# stm32-lqfp64-enc28j60.net
KiCad netlist of a schematic drawn in EAGLE
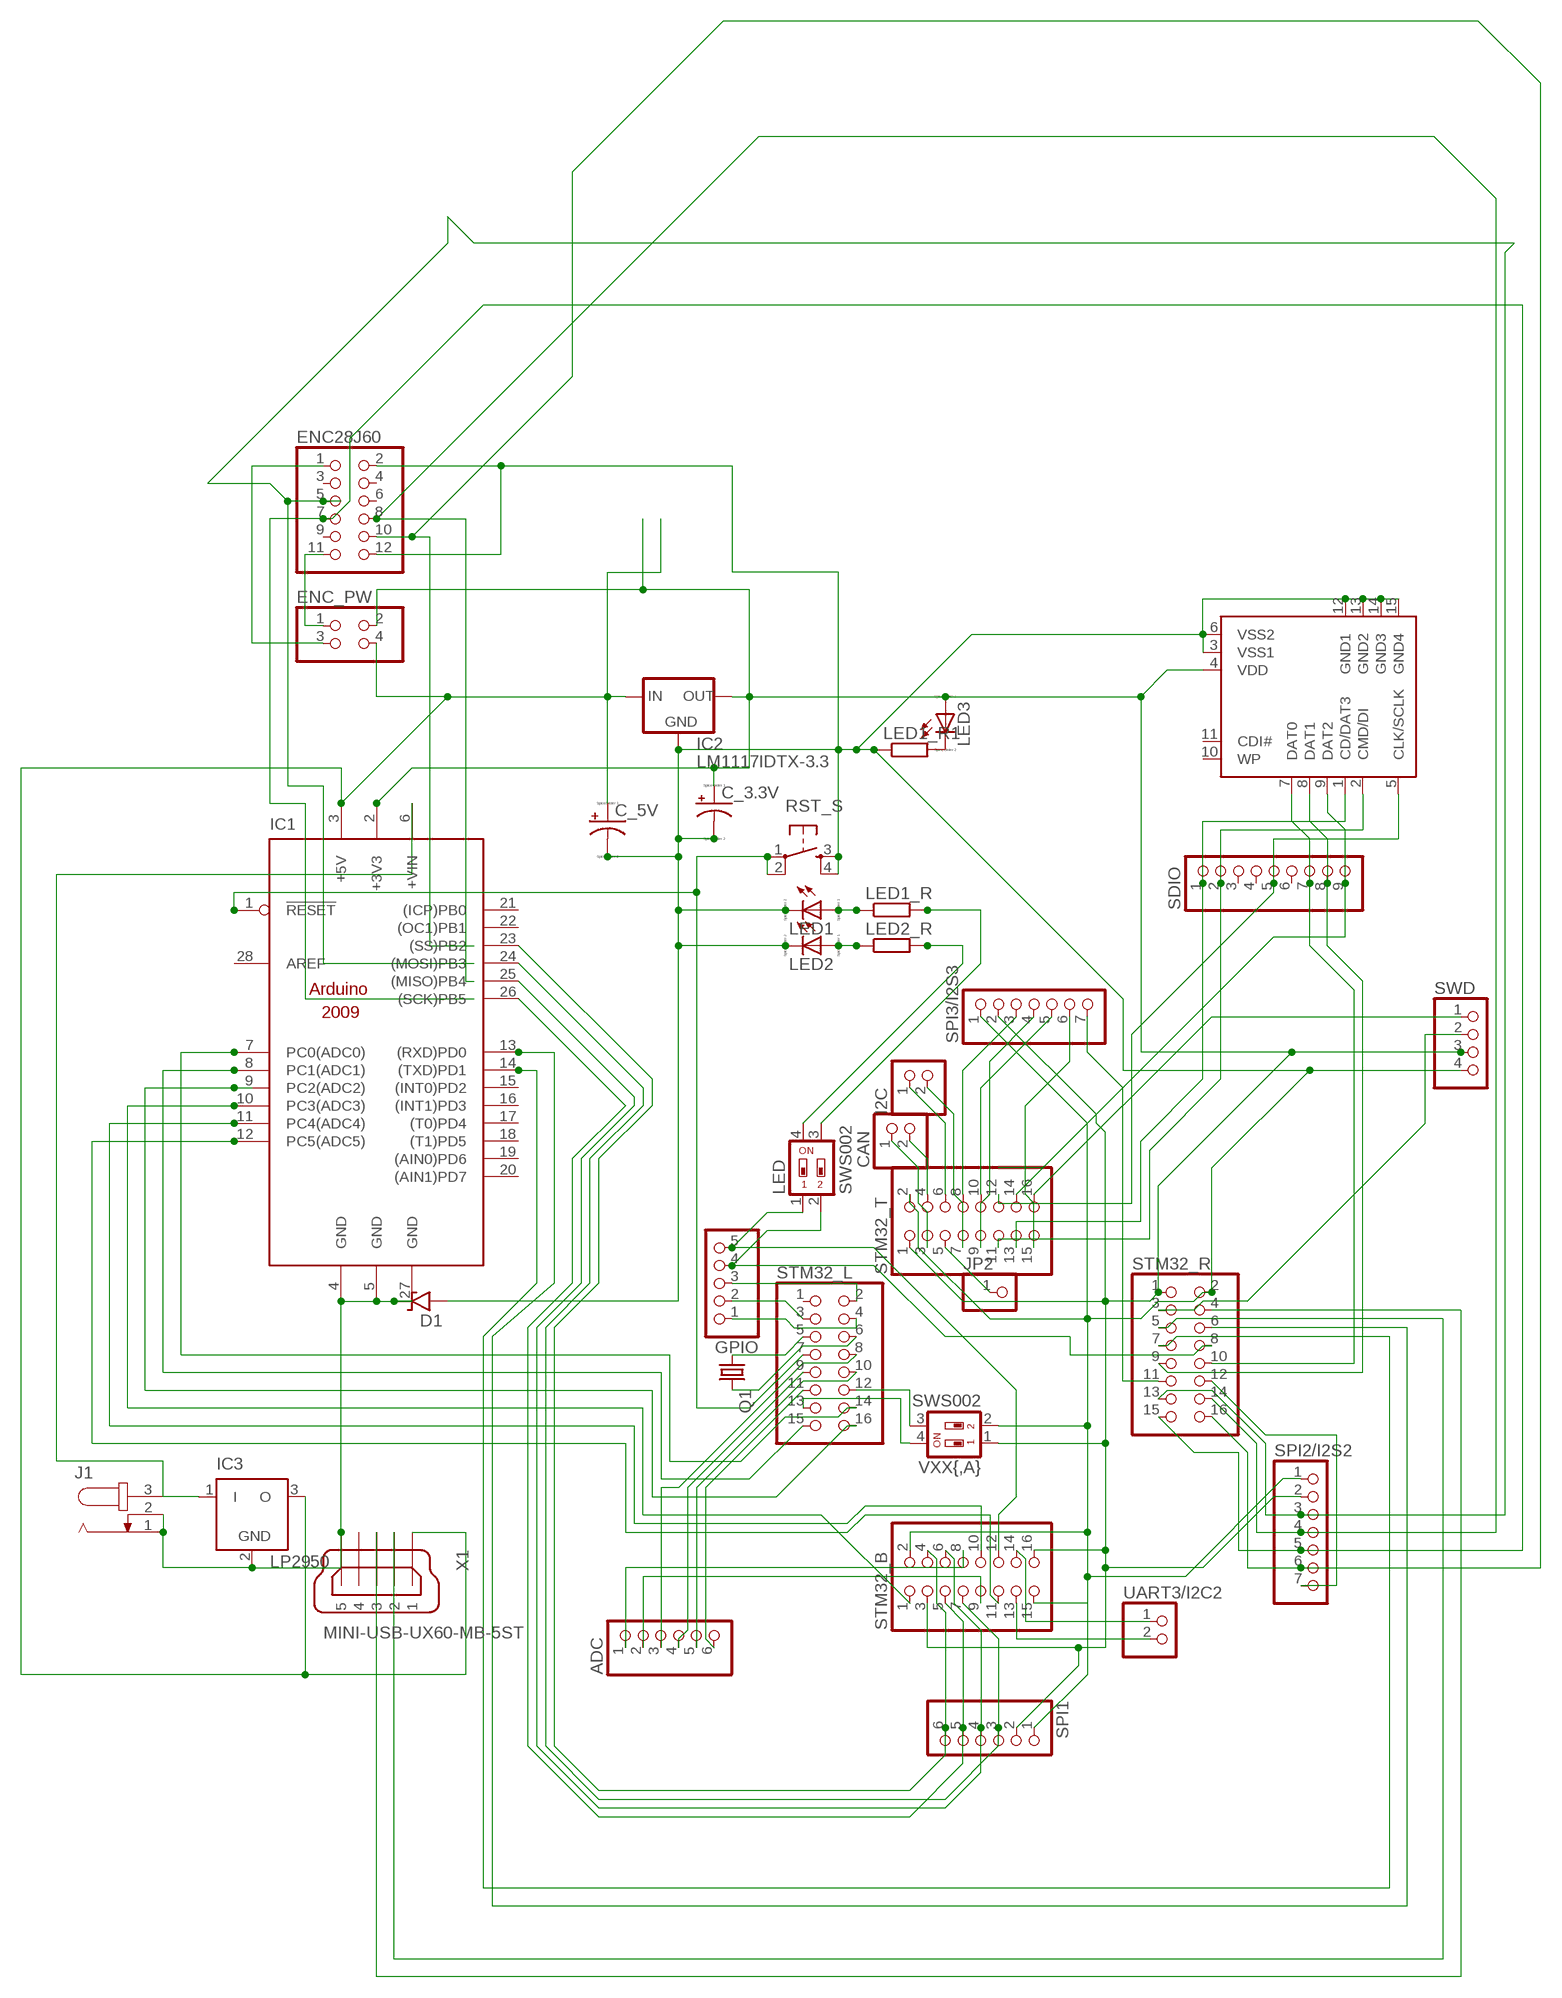
[diagram p0: schematic, sheet 1]

(export (version "E")
  (design (tool "Eeschema 10.0.6"))
  (components
    (comp (ref "ADC")
      (value "PINHD-1X06_2.54-S")
      (footprint "eagle-import:1X06-S")
      (libsource (lib "eagle-import") (part "PINHD-1X06_2.54-S"))
    )
    (comp (ref "CAN")
      (value "PINHD-1X02_2.54-S")
      (footprint "eagle-import:1X02-S")
      (libsource (lib "eagle-import") (part "PINHD-1X02_2.54-S"))
    )
    (comp (ref "C_3.3V")
      (value "CPOL-USE3.5-8")
      (footprint "eagle-import:E3,5-8")
      (libsource (lib "eagle-import") (part "CPOL-USE3.5-8"))
    )
    (comp (ref "C_5V")
      (value "CPOL-USE3.5-8")
      (footprint "eagle-import:E3,5-8")
      (libsource (lib "eagle-import") (part "CPOL-USE3.5-8"))
    )
    (comp (ref "D1")
      (value "1N9ZENER2")
      (footprint "eagle-import:DO35-2")
      (libsource (lib "eagle-import") (part "1N9ZENER2"))
    )
    (comp (ref "ENC28J60")
      (value "PINHD-2X6_2.54")
      (footprint "eagle-import:2X06")
      (libsource (lib "eagle-import") (part "PINHD-2X6_2.54"))
    )
    (comp (ref "ENC_PW")
      (value "PINHD-2X2_2.54")
      (footprint "eagle-import:2X02")
      (libsource (lib "eagle-import") (part "PINHD-2X2_2.54"))
    )
    (comp (ref "GPIO")
      (value "PINHD-1X05_2.54-S")
      (footprint "eagle-import:1X05-S")
      (libsource (lib "eagle-import") (part "PINHD-1X05_2.54-S"))
    )
    (comp (ref "I2C")
      (value "PINHD-1X02_2.54-S")
      (footprint "eagle-import:1X02-S")
      (libsource (lib "eagle-import") (part "PINHD-1X02_2.54-S"))
    )
    (comp (ref "IC1")
      (value "ARDUINO2009_PIN_12")
      (footprint "eagle-import:ARDUINO2009_2")
      (libsource (lib "eagle-import") (part "ARDUINO2009_PIN_12"))
    )
    (comp (ref "IC2")
      (value "LM1117IDTX-3.3")
      (footprint "eagle-import:TO252")
      (libsource (lib "eagle-import") (part "LM1117IDTX-3.3"))
    )
    (comp (ref "IC3")
      (value "LP2950")
      (footprint "eagle-import:DPACK")
      (libsource (lib "eagle-import") (part "LP2950"))
    )
    (comp (ref "J1")
      (value "JACK-PLUG0")
      (footprint "eagle-import:SPC4077")
      (libsource (lib "eagle-import") (part "JACK-PLUG0"))
    )
    (comp (ref "JP2")
      (value "PINHD-1X01_2.54-S")
      (footprint "eagle-import:1X01-S")
      (libsource (lib "eagle-import") (part "PINHD-1X01_2.54-S"))
    )
    (comp (ref "LED")
      (value "SWS002")
      (footprint "eagle-import:SMS-002")
      (libsource (lib "eagle-import") (part "SWS002"))
    )
    (comp (ref "LED1")
      (value "LED_ELD260")
      (footprint "eagle-import:LED_LD260")
      (libsource (lib "eagle-import") (part "LED_ELD260"))
    )
    (comp (ref "LED1_R")
      (value "R-EU_0204/7")
      (footprint "eagle-import:0204_7")
      (libsource (lib "eagle-import") (part "R-EU_0204/7"))
    )
    (comp (ref "LED1_R1")
      (value "R-EU_0204/7")
      (footprint "eagle-import:0204_7")
      (libsource (lib "eagle-import") (part "R-EU_0204/7"))
    )
    (comp (ref "LED2")
      (value "LED_ELD260")
      (footprint "eagle-import:LED_LD260")
      (libsource (lib "eagle-import") (part "LED_ELD260"))
    )
    (comp (ref "LED2_R")
      (value "R-EU_0204/7")
      (footprint "eagle-import:0204_7")
      (libsource (lib "eagle-import") (part "R-EU_0204/7"))
    )
    (comp (ref "LED3")
      (value "LED_ELD260")
      (footprint "eagle-import:LED_LD260")
      (libsource (lib "eagle-import") (part "LED_ELD260"))
    )
    (comp (ref "Q1")
      (value "CRYSTALHC49S")
      (footprint "eagle-import:HC49_S")
      (libsource (lib "eagle-import") (part "CRYSTALHC49S"))
    )
    (comp (ref "RST_S")
      (value "TAC_SWITCHPTH")
      (footprint "eagle-import:TACTILE-PTH")
      (libsource (lib "eagle-import") (part "TAC_SWITCHPTH"))
    )
    (comp (ref "SDIO")
      (value "PINHD-1X09_2.54-S")
      (footprint "eagle-import:1X09-S")
      (libsource (lib "eagle-import") (part "PINHD-1X09_2.54-S"))
    )
    (comp (ref "SPI1")
      (value "PINHD-1X06_2.54-S")
      (footprint "eagle-import:1X06-S")
      (libsource (lib "eagle-import") (part "PINHD-1X06_2.54-S"))
    )
    (comp (ref "SPI2/I2S2")
      (value "PINHD-1X07_2.54-S")
      (footprint "eagle-import:1X07-S")
      (libsource (lib "eagle-import") (part "PINHD-1X07_2.54-S"))
    )
    (comp (ref "SPI3/I2S3")
      (value "PINHD-1X07_2.54-S")
      (footprint "eagle-import:1X07-S")
      (libsource (lib "eagle-import") (part "PINHD-1X07_2.54-S"))
    )
    (comp (ref "STM32_B")
      (value "PINHD-2X08_2.54")
      (footprint "eagle-import:2X08")
      (libsource (lib "eagle-import") (part "PINHD-2X08_2.54"))
    )
    (comp (ref "STM32_L")
      (value "PINHD-2X08_2.54")
      (footprint "eagle-import:2X08")
      (libsource (lib "eagle-import") (part "PINHD-2X08_2.54"))
    )
    (comp (ref "STM32_R")
      (value "PINHD-2X08_2.54")
      (footprint "eagle-import:2X08")
      (libsource (lib "eagle-import") (part "PINHD-2X08_2.54"))
    )
    (comp (ref "STM32_T")
      (value "PINHD-2X08_2.54")
      (footprint "eagle-import:2X08")
      (libsource (lib "eagle-import") (part "PINHD-2X08_2.54"))
    )
    (comp (ref "SWD")
      (value "PINHD-1X4")
      (footprint "eagle-import:1X04")
      (libsource (lib "eagle-import") (part "PINHD-1X4"))
    )
    (comp (ref "U$2")
      (value "SDCARDVAR1")
      (footprint "eagle-import:SDCMF-10915W010")
      (libsource (lib "eagle-import") (part "SDCARDVAR1"))
    )
    (comp (ref "UART3/I2C2")
      (value "PINHD-1X02_2.54-S")
      (footprint "eagle-import:1X02-S")
      (libsource (lib "eagle-import") (part "PINHD-1X02_2.54-S"))
    )
    (comp (ref "VXX{,A}")
      (value "SWS002")
      (footprint "eagle-import:SMS-002")
      (libsource (lib "eagle-import") (part "SWS002"))
    )
    (comp (ref "X1")
      (value "MINI-USB-UX60-MB-5ST")
      (footprint "eagle-import:UX60-MB-5ST")
      (libsource (lib "eagle-import") (part "MINI-USB-UX60-MB-5ST"))
    )
  )
  (nets
    (net (code "1") (name "Net-(ADC-Pad1)") (class "Default")
      (node (ref "ADC") (pin "1") (pinfunction "1_1") (pintype "passive"))
      (node (ref "STM32_B") (pin "8") (pinfunction "8_8") (pintype "passive"))
    )
    (net (code "2") (name "Net-(ADC-Pad2)") (class "Default")
      (node (ref "ADC") (pin "2") (pinfunction "2_2") (pintype "passive"))
      (node (ref "STM32_B") (pin "9") (pinfunction "9_9") (pintype "passive"))
    )
    (net (code "3") (name "Net-(ADC-Pad3)") (class "Default")
      (node (ref "ADC") (pin "3") (pinfunction "3_3") (pintype "passive"))
      (node (ref "STM32_L") (pin "8") (pinfunction "8_8") (pintype "passive"))
    )
    (net (code "4") (name "Net-(ADC-Pad4)") (class "Default")
      (node (ref "ADC") (pin "4") (pinfunction "4_4") (pintype "passive"))
      (node (ref "STM32_L") (pin "9") (pinfunction "9_9") (pintype "passive"))
    )
    (net (code "5") (name "Net-(ADC-Pad5)") (class "Default")
      (node (ref "ADC") (pin "5") (pinfunction "5_5") (pintype "passive"))
      (node (ref "STM32_L") (pin "10") (pinfunction "10_10") (pintype "passive"))
    )
    (net (code "6") (name "Net-(ADC-Pad6)") (class "Default")
      (node (ref "ADC") (pin "6") (pinfunction "6_6") (pintype "passive"))
      (node (ref "STM32_L") (pin "11") (pinfunction "11_11") (pintype "passive"))
    )
    (net (code "7") (name "Net-(CAN-Pad1)") (class "Default")
      (node (ref "CAN") (pin "1") (pinfunction "1_1") (pintype "passive"))
      (node (ref "STM32_T") (pin "3") (pinfunction "3_3") (pintype "passive"))
    )
    (net (code "8") (name "Net-(CAN-Pad2)") (class "Default")
      (node (ref "CAN") (pin "2") (pinfunction "2_2") (pintype "passive"))
      (node (ref "STM32_T") (pin "4") (pinfunction "4_4") (pintype "passive"))
    )
    (net (code "9") (name "Net-(ENC28J60-Pad1)") (class "Default")
      (node (ref "ENC28J60") (pin "1") (pinfunction "1_1") (pintype "passive"))
      (node (ref "ENC_PW") (pin "3") (pinfunction "3_3") (pintype "passive"))
    )
    (net (code "10") (name "Net-(ENC28J60-Pad5)") (class "Default")
      (node (ref "ENC28J60") (pin "5") (pinfunction "5_5") (pintype "passive"))
      (node (ref "SPI2/I2S2") (pin "3") (pinfunction "3_3") (pintype "passive"))
      (node (ref "STM32_R") (pin "13") (pinfunction "13_13") (pintype "passive"))
    )
    (net (code "11") (name "Net-(ENC28J60-Pad7)") (class "Default")
      (node (ref "ENC28J60") (pin "7") (pinfunction "7_7") (pintype "passive"))
      (node (ref "SPI2/I2S2") (pin "5") (pinfunction "5_5") (pintype "passive"))
      (node (ref "STM32_R") (pin "15") (pinfunction "15_15") (pintype "passive"))
    )
    (net (code "12") (name "Net-(ENC28J60-Pad8)") (class "Default")
      (node (ref "ENC28J60") (pin "8") (pinfunction "8_8") (pintype "passive"))
      (node (ref "SPI2/I2S2") (pin "4") (pinfunction "4_4") (pintype "passive"))
      (node (ref "STM32_R") (pin "14") (pinfunction "14_14") (pintype "passive"))
    )
    (net (code "13") (name "Net-(ENC28J60-Pad10)") (class "Default")
      (node (ref "ENC28J60") (pin "10") (pinfunction "10_10") (pintype "passive"))
      (node (ref "SPI2/I2S2") (pin "6") (pinfunction "6_6") (pintype "passive"))
      (node (ref "STM32_R") (pin "16") (pinfunction "16_16") (pintype "passive"))
    )
    (net (code "14") (name "Net-(ENC28J60-Pad11)") (class "Default")
      (node (ref "ENC28J60") (pin "11") (pinfunction "11_11") (pintype "passive"))
      (node (ref "ENC_PW") (pin "1") (pinfunction "1_1") (pintype "passive"))
    )
    (net (code "15") (name "Net-(GPIO-Pad1)") (class "Default")
      (node (ref "GPIO") (pin "1") (pinfunction "1_1") (pintype "passive"))
      (node (ref "STM32_L") (pin "4") (pinfunction "4_4") (pintype "passive"))
    )
    (net (code "16") (name "Net-(GPIO-Pad2)") (class "Default")
      (node (ref "GPIO") (pin "2") (pinfunction "2_2") (pintype "passive"))
      (node (ref "STM32_L") (pin "3") (pinfunction "3_3") (pintype "passive"))
    )
    (net (code "17") (name "Net-(GPIO-Pad3)") (class "Default")
      (node (ref "GPIO") (pin "3") (pinfunction "3_3") (pintype "passive"))
      (node (ref "STM32_L") (pin "2") (pinfunction "2_2") (pintype "passive"))
    )
    (net (code "18") (name "Net-(GPIO-Pad4)") (class "Default")
      (node (ref "GPIO") (pin "4") (pinfunction "4_4") (pintype "passive"))
      (node (ref "LED") (pin "2") (pinfunction "2_2") (pintype "passive"))
      (node (ref "STM32_R") (pin "8") (pinfunction "8_8") (pintype "passive"))
    )
    (net (code "19") (name "Net-(GPIO-Pad5)") (class "Default")
      (node (ref "GPIO") (pin "5") (pinfunction "5_5") (pintype "passive"))
      (node (ref "LED") (pin "1") (pinfunction "1_1") (pintype "passive"))
      (node (ref "STM32_B") (pin "12") (pinfunction "12_12") (pintype "passive"))
    )
    (net (code "20") (name "Net-(I2C-Pad1)") (class "Default")
      (node (ref "I2C") (pin "1") (pinfunction "1_1") (pintype "passive"))
      (node (ref "STM32_T") (pin "6") (pinfunction "6_6") (pintype "passive"))
    )
    (net (code "21") (name "Net-(I2C-Pad2)") (class "Default")
      (node (ref "I2C") (pin "2") (pinfunction "2_2") (pintype "passive"))
      (node (ref "STM32_T") (pin "7") (pinfunction "7_7") (pintype "passive"))
    )
    (net (code "22") (name "Net-(IC1-(MISO)PB4)") (class "Default")
      (node (ref "IC1") (pin "25") (pinfunction "(MISO)PB4_25") (pintype "bidirectional"))
      (node (ref "SPI1") (pin "4") (pinfunction "4_4") (pintype "passive"))
      (node (ref "STM32_B") (pin "6") (pinfunction "6_6") (pintype "passive"))
    )
    (net (code "23") (name "Net-(IC1-(MOSI)PB3)") (class "Default")
      (node (ref "IC1") (pin "24") (pinfunction "(MOSI)PB3_24") (pintype "bidirectional"))
      (node (ref "SPI1") (pin "3") (pinfunction "3_3") (pintype "passive"))
      (node (ref "STM32_B") (pin "7") (pinfunction "7_7") (pintype "passive"))
    )
    (net (code "24") (name "Net-(IC1-(RXD)PD0)") (class "Default")
      (node (ref "IC1") (pin "13") (pinfunction "(RXD)PD0_13") (pintype "bidirectional"))
      (node (ref "STM32_R") (pin "6") (pinfunction "6_6") (pintype "passive"))
    )
    (net (code "25") (name "Net-(IC1-(SCK)PB5)") (class "Default")
      (node (ref "IC1") (pin "26") (pinfunction "(SCK)PB5_26") (pintype "bidirectional"))
      (node (ref "SPI1") (pin "5") (pinfunction "5_5") (pintype "passive"))
      (node (ref "STM32_B") (pin "5") (pinfunction "5_5") (pintype "passive"))
    )
    (net (code "26") (name "Net-(IC1-(SS)PB2)") (class "Default")
      (node (ref "IC1") (pin "23") (pinfunction "(SS)PB2_23") (pintype "bidirectional"))
      (node (ref "SPI1") (pin "6") (pinfunction "6_6") (pintype "passive"))
      (node (ref "STM32_B") (pin "4") (pinfunction "4_4") (pintype "passive"))
    )
    (net (code "27") (name "Net-(IC1-(TXD)PD1)") (class "Default")
      (node (ref "IC1") (pin "14") (pinfunction "(TXD)PD1_14") (pintype "bidirectional"))
      (node (ref "STM32_R") (pin "7") (pinfunction "7_7") (pintype "passive"))
    )
    (net (code "28") (name "Net-(IC1-+3V3)") (class "Default")
      (node (ref "C_3.3V") (pin "+") (pinfunction "+_+") (pintype "passive"))
      (node (ref "ENC_PW") (pin "2") (pinfunction "2_2") (pintype "passive"))
      (node (ref "IC1") (pin "2") (pinfunction "+3V3_2") (pintype "power_in"))
      (node (ref "IC2") (pin "TAB") (pinfunction "OUT_TAB") (pintype "passive"))
      (node (ref "LED3") (pin "A") (pinfunction "A_A") (pintype "passive"))
      (node (ref "SPI1") (pin "2") (pinfunction "2_2") (pintype "passive"))
      (node (ref "SPI2/I2S2") (pin "2") (pinfunction "2_2") (pintype "passive"))
      (node (ref "SPI3/I2S3") (pin "2") (pinfunction "2_2") (pintype "passive"))
      (node (ref "STM32_B") (pin "16") (pinfunction "16_16") (pintype "passive"))
      (node (ref "STM32_B") (pin "3") (pinfunction "3_3") (pintype "passive"))
      (node (ref "STM32_R") (pin "1") (pinfunction "1_1") (pintype "passive"))
      (node (ref "STM32_T") (pin "1") (pinfunction "1_1") (pintype "passive"))
      (node (ref "SWD") (pin "3") (pinfunction "3_3") (pintype "passive"))
      (node (ref "U$2") (pin "4") (pinfunction "VDD_4") (pintype "power_in"))
      (node (ref "VXX{,A}") (pin "1") (pinfunction "1_1") (pintype "passive"))
    )
    (net (code "29") (name "Net-(IC1-+5V)") (class "Default")
      (node (ref "C_5V") (pin "+") (pinfunction "+_+") (pintype "passive"))
      (node (ref "ENC_PW") (pin "4") (pinfunction "4_4") (pintype "passive"))
      (node (ref "IC1") (pin "3") (pinfunction "+5V_3") (pintype "power_in"))
      (node (ref "IC2") (pin "2") (pinfunction "IN_2") (pintype "input"))
      (node (ref "IC3") (pin "3") (pinfunction "O_3") (pintype "input"))
      (node (ref "X1") (pin "1") (pinfunction "1_1") (pintype "input"))
    )
    (net (code "30") (name "Net-(IC1-+VIN)") (class "Default")
      (node (ref "IC1") (pin "6") (pinfunction "+VIN_6") (pintype "bidirectional"))
      (node (ref "IC3") (pin "1") (pinfunction "I_1") (pintype "input"))
      (node (ref "J1") (pin "3") (pinfunction "3_3") (pintype "passive"))
    )
    (net (code "31") (name "Net-(IC1-PC0(ADC0))") (class "Default")
      (node (ref "IC1") (pin "7") (pinfunction "PC0(ADC0)_7") (pintype "bidirectional"))
      (node (ref "STM32_L") (pin "14") (pinfunction "14_14") (pintype "passive"))
    )
    (net (code "32") (name "Net-(IC1-PC1(ADC1))") (class "Default")
      (node (ref "IC1") (pin "8") (pinfunction "PC1(ADC1)_8") (pintype "bidirectional"))
      (node (ref "STM32_L") (pin "15") (pinfunction "15_15") (pintype "passive"))
    )
    (net (code "33") (name "Net-(IC1-PC2(ADC2))") (class "Default")
      (node (ref "IC1") (pin "9") (pinfunction "PC2(ADC2)_9") (pintype "bidirectional"))
      (node (ref "STM32_L") (pin "16") (pinfunction "16_16") (pintype "passive"))
    )
    (net (code "34") (name "Net-(IC1-PC3(ADC3))") (class "Default")
      (node (ref "IC1") (pin "10") (pinfunction "PC3(ADC3)_10") (pintype "bidirectional"))
      (node (ref "STM32_B") (pin "1") (pinfunction "1_1") (pintype "passive"))
    )
    (net (code "35") (name "Net-(IC1-PC4(ADC4))") (class "Default")
      (node (ref "IC1") (pin "11") (pinfunction "PC4(ADC4)_11") (pintype "bidirectional"))
      (node (ref "STM32_B") (pin "10") (pinfunction "10_10") (pintype "passive"))
    )
    (net (code "36") (name "Net-(IC1-PC5(ADC5))") (class "Default")
      (node (ref "IC1") (pin "12") (pinfunction "PC5(ADC5)_12") (pintype "bidirectional"))
      (node (ref "STM32_B") (pin "11") (pinfunction "11_11") (pintype "passive"))
    )
    (net (code "37") (name "Net-(IC1-~{RESET})") (class "Default")
      (node (ref "IC1") (pin "1") (pinfunction "~{RESET}_1") (pintype "bidirectional"))
      (node (ref "RST_S") (pin "1") (pinfunction "1_1") (pintype "passive"))
      (node (ref "RST_S") (pin "2") (pinfunction "2_2") (pintype "passive"))
      (node (ref "STM32_L") (pin "7") (pinfunction "7_7") (pintype "passive"))
    )
    (net (code "38") (name "Net-(IC2-GND)") (class "Default")
      (node (ref "C_3.3V") (pin "-") (pinfunction "-_-") (pintype "passive"))
      (node (ref "C_5V") (pin "-") (pinfunction "-_-") (pintype "passive"))
      (node (ref "D1") (pin "A") (pinfunction "A_A") (pintype "passive"))
      (node (ref "ENC28J60") (pin "12") (pinfunction "12_12") (pintype "passive"))
      (node (ref "ENC28J60") (pin "2") (pinfunction "2_2") (pintype "passive"))
      (node (ref "IC2") (pin "1") (pinfunction "GND_1") (pintype "input"))
      (node (ref "LED1") (pin "K") (pinfunction "C_K") (pintype "passive"))
      (node (ref "LED1_R1") (pin "1") (pinfunction "1_1") (pintype "passive"))
      (node (ref "LED2") (pin "K") (pinfunction "C_K") (pintype "passive"))
      (node (ref "RST_S") (pin "3") (pinfunction "3_3") (pintype "passive"))
      (node (ref "RST_S") (pin "4") (pinfunction "4_4") (pintype "passive"))
      (node (ref "SPI1") (pin "1") (pinfunction "1_1") (pintype "passive"))
      (node (ref "SPI2/I2S2") (pin "1") (pinfunction "1_1") (pintype "passive"))
      (node (ref "SPI3/I2S3") (pin "1") (pinfunction "1_1") (pintype "passive"))
      (node (ref "STM32_B") (pin "15") (pinfunction "15_15") (pintype "passive"))
      (node (ref "STM32_B") (pin "2") (pinfunction "2_2") (pintype "passive"))
      (node (ref "STM32_R") (pin "2") (pinfunction "2_2") (pintype "passive"))
      (node (ref "STM32_T") (pin "2") (pinfunction "2_2") (pintype "passive"))
      (node (ref "SWD") (pin "4") (pinfunction "4_4") (pintype "passive"))
      (node (ref "U$2") (pin "12") (pinfunction "GND1_12") (pintype "power_in"))
      (node (ref "U$2") (pin "13") (pinfunction "GND2_13") (pintype "power_in"))
      (node (ref "U$2") (pin "14") (pinfunction "GND3_14") (pintype "power_in"))
      (node (ref "U$2") (pin "15") (pinfunction "GND4_15") (pintype "power_in"))
      (node (ref "U$2") (pin "3") (pinfunction "VSS1_3") (pintype "power_in"))
      (node (ref "U$2") (pin "6") (pinfunction "VSS2_6") (pintype "power_in"))
      (node (ref "VXX{,A}") (pin "2") (pinfunction "2_2") (pintype "passive"))
    )
    (net (code "39") (name "Net-(IC3-GND)") (class "Default")
      (node (ref "D1") (pin "C") (pinfunction "C_C") (pintype "passive"))
      (node (ref "IC1") (pin "27") (pinfunction "GND_27") (pintype "power_in"))
      (node (ref "IC1") (pin "4") (pinfunction "GND_4") (pintype "power_in"))
      (node (ref "IC1") (pin "5") (pinfunction "GND_5") (pintype "power_in"))
      (node (ref "IC3") (pin "2") (pinfunction "GND_2") (pintype "power_in"))
      (node (ref "J1") (pin "1") (pinfunction "1_1") (pintype "passive"))
      (node (ref "J1") (pin "2") (pinfunction "2_2") (pintype "passive"))
      (node (ref "X1") (pin "5") (pinfunction "5_5") (pintype "input"))
    )
    (net (code "40") (name "Net-(JP2-Pad1)") (class "Default")
      (node (ref "JP2") (pin "1") (pinfunction "1_1") (pintype "passive"))
      (node (ref "STM32_T") (pin "5") (pinfunction "5_5") (pintype "passive"))
    )
    (net (code "41") (name "Net-(LED-Pad3)") (class "Default")
      (node (ref "LED") (pin "3") (pinfunction "3_3") (pintype "passive"))
      (node (ref "LED1_R") (pin "2") (pinfunction "2_2") (pintype "passive"))
    )
    (net (code "42") (name "Net-(LED-Pad4)") (class "Default")
      (node (ref "LED") (pin "4") (pinfunction "4_4") (pintype "passive"))
      (node (ref "LED2_R") (pin "2") (pinfunction "2_2") (pintype "passive"))
    )
    (net (code "43") (name "Net-(LED1-PadA)") (class "Default")
      (node (ref "LED1") (pin "A") (pinfunction "A_A") (pintype "passive"))
      (node (ref "LED1_R") (pin "1") (pinfunction "1_1") (pintype "passive"))
    )
    (net (code "44") (name "Net-(LED2-PadA)") (class "Default")
      (node (ref "LED2") (pin "A") (pinfunction "A_A") (pintype "passive"))
      (node (ref "LED2_R") (pin "1") (pinfunction "1_1") (pintype "passive"))
    )
    (net (code "45") (name "Net-(LED3-C)") (class "Default")
      (node (ref "LED1_R1") (pin "2") (pinfunction "2_2") (pintype "passive"))
      (node (ref "LED3") (pin "K") (pinfunction "C_K") (pintype "passive"))
    )
    (net (code "46") (name "Net-(Q1-Pad1)") (class "Default")
      (node (ref "Q1") (pin "1") (pinfunction "1_1") (pintype "passive"))
      (node (ref "STM32_L") (pin "5") (pinfunction "5_5") (pintype "passive"))
    )
    (net (code "47") (name "Net-(Q1-Pad2)") (class "Default")
      (node (ref "Q1") (pin "2") (pinfunction "2_2") (pintype "passive"))
      (node (ref "STM32_L") (pin "6") (pinfunction "6_6") (pintype "passive"))
    )
    (net (code "48") (name "Net-(SPI2/I2S2-Pad7)") (class "Default")
      (node (ref "SPI2/I2S2") (pin "7") (pinfunction "7_7") (pintype "passive"))
      (node (ref "STM32_R") (pin "12") (pinfunction "12_12") (pintype "passive"))
    )
    (net (code "49") (name "Net-(SPI3/I2S3-Pad3)") (class "Default")
      (node (ref "SPI3/I2S3") (pin "3") (pinfunction "3_3") (pintype "passive"))
      (node (ref "STM32_T") (pin "8") (pinfunction "8_8") (pintype "passive"))
    )
    (net (code "50") (name "Net-(SPI3/I2S3-Pad4)") (class "Default")
      (node (ref "SPI3/I2S3") (pin "4") (pinfunction "4_4") (pintype "passive"))
      (node (ref "STM32_T") (pin "9") (pinfunction "9_9") (pintype "passive"))
    )
    (net (code "51") (name "Net-(SPI3/I2S3-Pad5)") (class "Default")
      (node (ref "SPI3/I2S3") (pin "5") (pinfunction "5_5") (pintype "passive"))
      (node (ref "STM32_T") (pin "10") (pinfunction "10_10") (pintype "passive"))
    )
    (net (code "52") (name "Net-(SPI3/I2S3-Pad6)") (class "Default")
      (node (ref "SPI3/I2S3") (pin "6") (pinfunction "6_6") (pintype "passive"))
      (node (ref "STM32_T") (pin "15") (pinfunction "15_15") (pintype "passive"))
    )
    (net (code "53") (name "Net-(SPI3/I2S3-Pad7)") (class "Default")
      (node (ref "SPI3/I2S3") (pin "7") (pinfunction "7_7") (pintype "passive"))
      (node (ref "STM32_R") (pin "11") (pinfunction "11_11") (pintype "passive"))
    )
    (net (code "54") (name "Net-(STM32_B-Pad13)") (class "Default")
      (node (ref "STM32_B") (pin "13") (pinfunction "13_13") (pintype "passive"))
      (node (ref "UART3/I2C2") (pin "2") (pinfunction "2_2") (pintype "passive"))
    )
    (net (code "55") (name "Net-(STM32_B-Pad14)") (class "Default")
      (node (ref "STM32_B") (pin "14") (pinfunction "14_14") (pintype "passive"))
      (node (ref "UART3/I2C2") (pin "1") (pinfunction "1_1") (pintype "passive"))
    )
    (net (code "56") (name "Net-(STM32_L-Pad12)") (class "Default")
      (node (ref "STM32_L") (pin "12") (pinfunction "12_12") (pintype "passive"))
      (node (ref "VXX{,A}") (pin "3") (pinfunction "3_3") (pintype "passive"))
    )
    (net (code "57") (name "Net-(STM32_L-Pad13)") (class "Default")
      (node (ref "STM32_L") (pin "13") (pinfunction "13_13") (pintype "passive"))
      (node (ref "VXX{,A}") (pin "4") (pinfunction "4_4") (pintype "passive"))
    )
    (net (code "58") (name "Net-(STM32_R-Pad3)") (class "Default")
      (node (ref "STM32_R") (pin "3") (pinfunction "3_3") (pintype "passive"))
      (node (ref "SWD") (pin "2") (pinfunction "2_2") (pintype "passive"))
    )
    (net (code "59") (name "Net-(STM32_R-Pad4)") (class "Default")
      (node (ref "STM32_R") (pin "4") (pinfunction "4_4") (pintype "passive"))
      (node (ref "X1") (pin "3") (pinfunction "3_3") (pintype "input"))
    )
    (net (code "60") (name "Net-(STM32_R-Pad5)") (class "Default")
      (node (ref "STM32_R") (pin "5") (pinfunction "5_5") (pintype "passive"))
      (node (ref "X1") (pin "2") (pinfunction "2_2") (pintype "input"))
    )
    (net (code "61") (name "Net-(STM32_T-Pad16)") (class "Default")
      (node (ref "STM32_T") (pin "16") (pinfunction "16_16") (pintype "passive"))
      (node (ref "SWD") (pin "1") (pinfunction "1_1") (pintype "passive"))
    )
    (net (code "62") (name "Net-(U$2-CD{slash}DAT3)") (class "Default")
      (node (ref "SDIO") (pin "1") (pinfunction "1_1") (pintype "passive"))
      (node (ref "STM32_T") (pin "13") (pinfunction "13_13") (pintype "passive"))
      (node (ref "U$2") (pin "1") (pinfunction "CD/DAT3_1") (pintype "bidirectional"))
    )
    (net (code "63") (name "Net-(U$2-CLK{slash}SCLK)") (class "Default")
      (node (ref "SDIO") (pin "5") (pinfunction "5_5") (pintype "passive"))
      (node (ref "STM32_T") (pin "12") (pinfunction "12_12") (pintype "passive"))
      (node (ref "U$2") (pin "5") (pinfunction "CLK/SCLK_5") (pintype "bidirectional"))
    )
    (net (code "64") (name "Net-(U$2-CMD{slash}DI)") (class "Default")
      (node (ref "SDIO") (pin "2") (pinfunction "2_2") (pintype "passive"))
      (node (ref "STM32_T") (pin "11") (pinfunction "11_11") (pintype "passive"))
      (node (ref "U$2") (pin "2") (pinfunction "CMD/DI_2") (pintype "bidirectional"))
    )
    (net (code "65") (name "Net-(U$2-DAT0)") (class "Default")
      (node (ref "SDIO") (pin "7") (pinfunction "7_7") (pintype "passive"))
      (node (ref "STM32_R") (pin "10") (pinfunction "10_10") (pintype "passive"))
      (node (ref "U$2") (pin "7") (pinfunction "DAT0_7") (pintype "bidirectional"))
    )
    (net (code "66") (name "Net-(U$2-DAT1)") (class "Default")
      (node (ref "SDIO") (pin "8") (pinfunction "8_8") (pintype "passive"))
      (node (ref "STM32_R") (pin "9") (pinfunction "9_9") (pintype "passive"))
      (node (ref "U$2") (pin "8") (pinfunction "DAT1_8") (pintype "bidirectional"))
    )
    (net (code "67") (name "Net-(U$2-DAT2)") (class "Default")
      (node (ref "SDIO") (pin "9") (pinfunction "9_9") (pintype "passive"))
      (node (ref "STM32_T") (pin "14") (pinfunction "14_14") (pintype "passive"))
      (node (ref "U$2") (pin "9") (pinfunction "DAT2_9") (pintype "bidirectional"))
    )
    (net (code "68") (name "unconnected-(ENC28J60-Pad3)") (class "Default")
      (node (ref "ENC28J60") (pin "3") (pinfunction "3_3") (pintype "passive"))
    )
    (net (code "69") (name "unconnected-(ENC28J60-Pad4)") (class "Default")
      (node (ref "ENC28J60") (pin "4") (pinfunction "4_4") (pintype "passive"))
    )
    (net (code "70") (name "unconnected-(ENC28J60-Pad6)") (class "Default")
      (node (ref "ENC28J60") (pin "6") (pinfunction "6_6") (pintype "passive"))
    )
    (net (code "71") (name "unconnected-(ENC28J60-Pad9)") (class "Default")
      (node (ref "ENC28J60") (pin "9") (pinfunction "9_9") (pintype "passive"))
    )
    (net (code "72") (name "unconnected-(IC1-(AIN0)PD6-Pad19)") (class "Default")
      (node (ref "IC1") (pin "19") (pinfunction "(AIN0)PD6_19") (pintype "bidirectional"))
    )
    (net (code "73") (name "unconnected-(IC1-(AIN1)PD7-Pad20)") (class "Default")
      (node (ref "IC1") (pin "20") (pinfunction "(AIN1)PD7_20") (pintype "bidirectional"))
    )
    (net (code "74") (name "unconnected-(IC1-(ICP)PB0-Pad21)") (class "Default")
      (node (ref "IC1") (pin "21") (pinfunction "(ICP)PB0_21") (pintype "bidirectional"))
    )
    (net (code "75") (name "unconnected-(IC1-(INT0)PD2-Pad15)") (class "Default")
      (node (ref "IC1") (pin "15") (pinfunction "(INT0)PD2_15") (pintype "bidirectional"))
    )
    (net (code "76") (name "unconnected-(IC1-(INT1)PD3-Pad16)") (class "Default")
      (node (ref "IC1") (pin "16") (pinfunction "(INT1)PD3_16") (pintype "bidirectional"))
    )
    (net (code "77") (name "unconnected-(IC1-(OC1)PB1-Pad22)") (class "Default")
      (node (ref "IC1") (pin "22") (pinfunction "(OC1)PB1_22") (pintype "bidirectional"))
    )
    (net (code "78") (name "unconnected-(IC1-(T0)PD4-Pad17)") (class "Default")
      (node (ref "IC1") (pin "17") (pinfunction "(T0)PD4_17") (pintype "bidirectional"))
    )
    (net (code "79") (name "unconnected-(IC1-(T1)PD5-Pad18)") (class "Default")
      (node (ref "IC1") (pin "18") (pinfunction "(T1)PD5_18") (pintype "bidirectional"))
    )
    (net (code "80") (name "unconnected-(IC1-AREF-Pad28)") (class "Default")
      (node (ref "IC1") (pin "28") (pinfunction "AREF_28") (pintype "bidirectional"))
    )
    (net (code "81") (name "unconnected-(SDIO-Pad3)") (class "Default")
      (node (ref "SDIO") (pin "3") (pinfunction "3_3") (pintype "passive"))
    )
    (net (code "82") (name "unconnected-(SDIO-Pad4)") (class "Default")
      (node (ref "SDIO") (pin "4") (pinfunction "4_4") (pintype "passive"))
    )
    (net (code "83") (name "unconnected-(SDIO-Pad6)") (class "Default")
      (node (ref "SDIO") (pin "6") (pinfunction "6_6") (pintype "passive"))
    )
    (net (code "84") (name "unconnected-(STM32_L-Pad1)") (class "Default")
      (node (ref "STM32_L") (pin "1") (pinfunction "1_1") (pintype "passive"))
    )
    (net (code "85") (name "unconnected-(U$2-CDI#-Pad11)") (class "Default")
      (node (ref "U$2") (pin "11") (pinfunction "CDI#_11") (pintype "output"))
    )
    (net (code "86") (name "unconnected-(U$2-WP-Pad10)") (class "Default")
      (node (ref "U$2") (pin "10") (pinfunction "WP_10") (pintype "output"))
    )
    (net (code "87") (name "unconnected-(X1-Pad4)") (class "Default")
      (node (ref "X1") (pin "4") (pinfunction "4_4") (pintype "input"))
    )
  )
)
